# Sheet1.net
KiCad netlist of a schematic drawn in Altium Designer
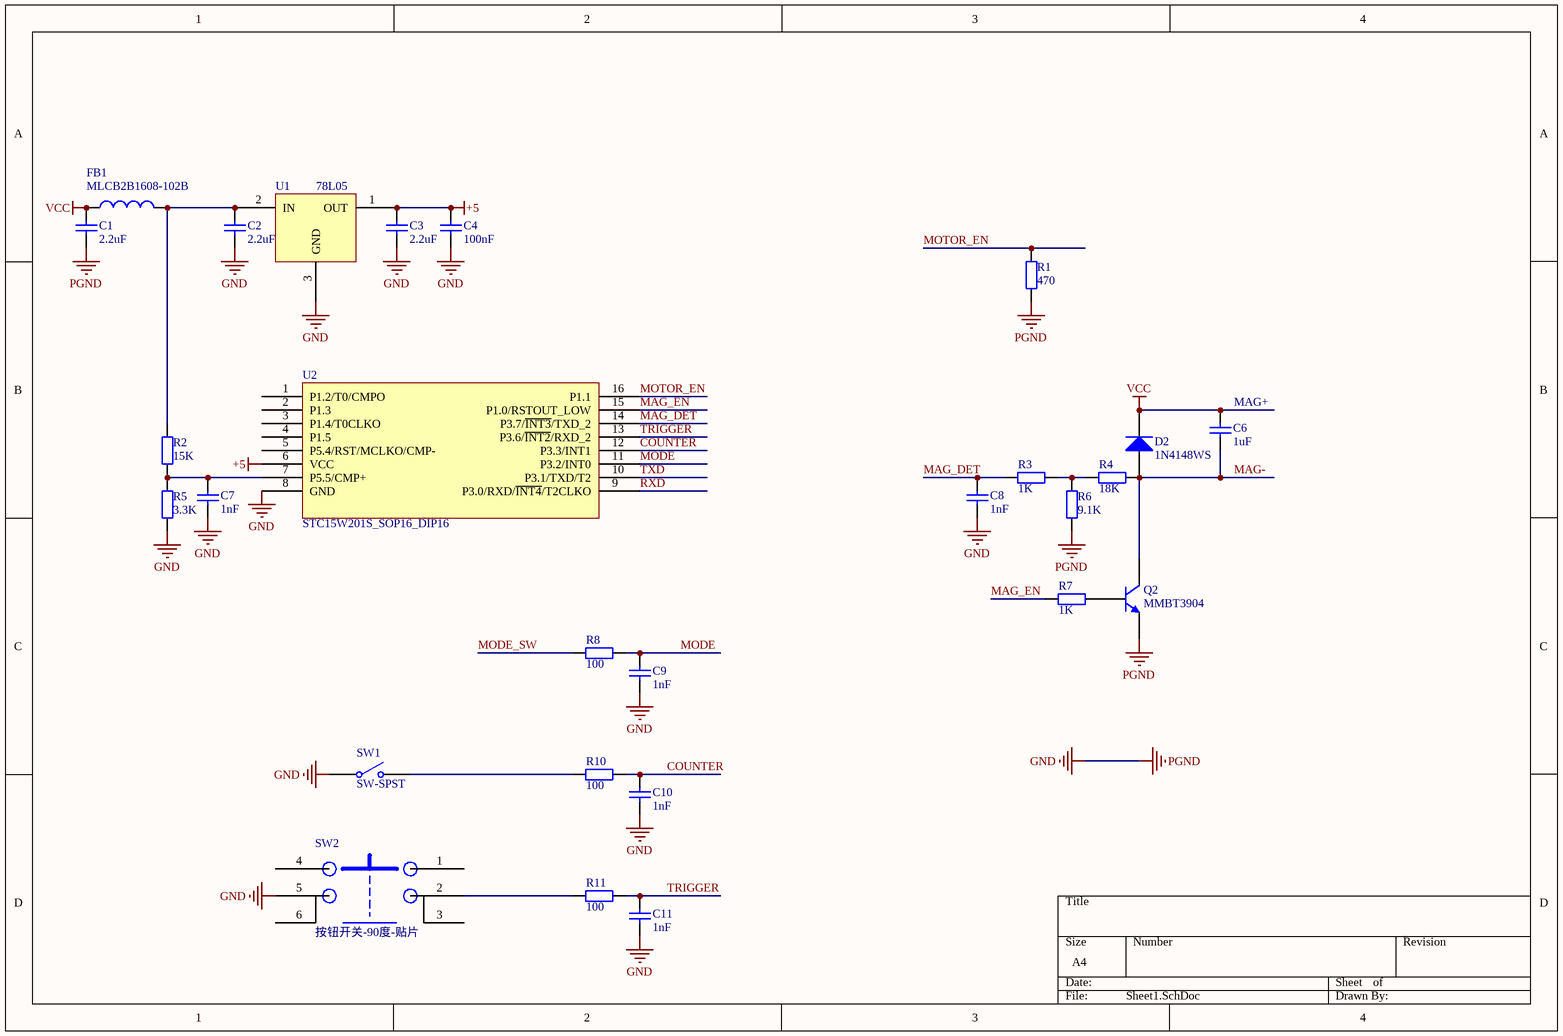
[diagram p0: Sheet1.SchDoc]

(export (version "E")
  (design (tool "Eeschema 10.0.6"))
  (components
    (comp (ref "C1")
      (value "2.2uF")
      (footprint "0805[cap]")
      (description "Chip Capacitor")
      (fields (field (name "Comment") "CT41L-0805-2C1-25V-225K"))
      (libsource (lib "passive") (part "Capacitor"))
    )
    (comp (ref "C2")
      (value "2.2uF")
      (footprint "0805[cap]")
      (description "Chip Capacitor")
      (fields (field (name "Comment") "CT41L-0805-2C1-25V-225K"))
      (libsource (lib "passive") (part "Capacitor"))
    )
    (comp (ref "C3")
      (value "2.2uF")
      (footprint "0805[cap]")
      (description "Chip Capacitor")
      (fields (field (name "Comment") "CT41L-0805-2C1-25V-225K"))
      (libsource (lib "passive") (part "Capacitor"))
    )
    (comp (ref "C4")
      (value "100nF")
      (footprint "0603[cap]")
      (description "Chip Capacitor")
      (fields (field (name "Comment") "CT41L-0603-2C1-50V-224K"))
      (libsource (lib "passive") (part "Capacitor"))
    )
    (comp (ref "C6")
      (value "1uF")
      (footprint "0603[cap]")
      (description "Chip Capacitor")
      (fields (field (name "Comment") "CT41L-0603-2C1-50V-224K"))
      (libsource (lib "passive") (part "Capacitor"))
    )
    (comp (ref "C7")
      (value "1nF")
      (footprint "0603[cap]")
      (description "Chip Capacitor")
      (fields (field (name "Comment") "CT41L-0603-2C1-50V-224K"))
      (libsource (lib "passive") (part "Capacitor"))
    )
    (comp (ref "C8")
      (value "1nF")
      (footprint "0603[cap]")
      (description "Chip Capacitor")
      (fields (field (name "Comment") "CT41L-0603-2C1-50V-224K"))
      (libsource (lib "passive") (part "Capacitor"))
    )
    (comp (ref "C9")
      (value "1nF")
      (footprint "0603[cap]")
      (description "Chip Capacitor")
      (fields (field (name "Comment") "CT41L-0603-2C1-50V-224K"))
      (libsource (lib "passive") (part "Capacitor"))
    )
    (comp (ref "C10")
      (value "1nF")
      (footprint "0603[cap]")
      (description "Chip Capacitor")
      (fields (field (name "Comment") "CT41L-0603-2C1-50V-224K"))
      (libsource (lib "passive") (part "Capacitor"))
    )
    (comp (ref "C11")
      (value "1nF")
      (footprint "0603[cap]")
      (description "Chip Capacitor")
      (fields (field (name "Comment") "CT41L-0603-2C1-50V-224K"))
      (libsource (lib "passive") (part "Capacitor"))
    )
    (comp (ref "D2")
      (value "1N4148WS")
      (footprint "SOD323")
      (description "Default Diode")
      (libsource (lib "Miscellaneous Devices") (part "Diode"))
    )
    (comp (ref "FB1")
      (value "MLCB2B1608-102B")
      (footprint "0603[bead]")
      (description "Chip Bead")
      (libsource (lib "passive") (part "bead"))
    )
    (comp (ref "Q2")
      (value "MMBT3904")
      (footprint "SOT23-3N")
      (description "NPN General Purpose Amplifier")
      (libsource (lib "transistor") (part "MMBT3904"))
    )
    (comp (ref "R1")
      (value "470")
      (footprint "0603[res]")
      (description "Resistor")
      (fields (field (name "Comment") "RMK1608MB102J"))
      (libsource (lib "") (part "Resistor_2"))
    )
    (comp (ref "R2")
      (value "15K")
      (footprint "0603[res]")
      (description "Resistor")
      (fields (field (name "Comment") "RMK1608MB102J"))
      (libsource (lib "") (part "Resistor_2"))
    )
    (comp (ref "R3")
      (value "1K")
      (footprint "0603[res]")
      (description "Resistor")
      (fields (field (name "Comment") "RMK1608MB102J"))
      (libsource (lib "passive") (part "Resistor"))
    )
    (comp (ref "R4")
      (value "18K")
      (footprint "0603[res]")
      (description "Resistor")
      (fields (field (name "Comment") "RMK1608MB102J"))
      (libsource (lib "") (part "Resistor_1"))
    )
    (comp (ref "R5")
      (value "3.3K")
      (footprint "0603[res]")
      (description "Resistor")
      (fields (field (name "Comment") "RMK1608MB102J"))
      (libsource (lib "") (part "Resistor_2"))
    )
    (comp (ref "R6")
      (value "9.1K")
      (footprint "0603[res]")
      (description "Resistor")
      (fields (field (name "Comment") "RMK1608MB102J"))
      (libsource (lib "") (part "Resistor_2"))
    )
    (comp (ref "R7")
      (value "1K")
      (footprint "0603[res]")
      (description "Resistor")
      (fields (field (name "Comment") "RMK1608MB102J"))
      (libsource (lib "passive") (part "Resistor"))
    )
    (comp (ref "R8")
      (value "100")
      (footprint "0603[res]")
      (description "Resistor")
      (fields (field (name "Comment") "RMK1608MB102J"))
      (libsource (lib "passive") (part "Resistor"))
    )
    (comp (ref "R10")
      (value "100")
      (footprint "0603[res]")
      (description "Resistor")
      (fields (field (name "Comment") "RMK1608MB102J"))
      (libsource (lib "passive") (part "Resistor"))
    )
    (comp (ref "R11")
      (value "100")
      (footprint "0603[res]")
      (description "Resistor")
      (fields (field (name "Comment") "RMK1608MB102J"))
      (libsource (lib "passive") (part "Resistor"))
    )
    (comp (ref "SW1")
      (value "SW-SPST")
      (footprint "JJJHRGG200NOPMRTR")
      (description "Single-Pole, Single-Throw Switch")
      (fields (field (name "PUBLISHER") "Altium Limited"))
      (libsource (lib "Miscellaneous Devices") (part "SW-SPST"))
    )
    (comp (ref "SW2")
      (value "按钮开关-90度-贴片")
      (footprint "按钮开关-90度-贴片")
      (libsource (lib "switch") (part "按钮开关-90度-贴片"))
    )
    (comp (ref "U1") (value "78L05") (footprint "SOT23-3N") (libsource (lib "power") (part "78L05")))
    (comp (ref "U2")
      (value "STC15W201S_SOP16_DIP16")
      (footprint "SOP16")
      (libsource (lib "stcmcu_altium_lib") (part "STC15W201S_SOP16_DIP16"))
    )
  )
  (nets
    (net (code "1") (name "+5") (class "Default")
      (node (ref "C3") (pin "1") (pinfunction "1_1") (pintype "passive"))
      (node (ref "C4") (pin "1") (pinfunction "1_1") (pintype "passive"))
      (node (ref "U1") (pin "1") (pinfunction "OUT_1") (pintype "passive"))
      (node (ref "U2") (pin "6") (pinfunction "VCC_6") (pintype "passive"))
    )
    (net (code "2") (name "/COUNTER") (class "Default")
      (node (ref "C10") (pin "1") (pinfunction "1_1") (pintype "passive"))
      (node (ref "R10") (pin "2") (pinfunction "2_2") (pintype "passive"))
      (node (ref "U2") (pin "12") (pinfunction "P3.3/INT1_12") (pintype "passive"))
    )
    (net (code "3") (name "/MAG-") (class "Default")
      (node (ref "C6") (pin "2") (pinfunction "2_2") (pintype "passive"))
      (node (ref "D2") (pin "1") (pinfunction "A_1") (pintype "passive"))
      (node (ref "Q2") (pin "3") (pinfunction "C_3") (pintype "passive"))
      (node (ref "R4") (pin "1") (pinfunction "1_1") (pintype "passive"))
    )
    (net (code "4") (name "/MAG_DET") (class "Default")
      (node (ref "C8") (pin "1") (pinfunction "1_1") (pintype "passive"))
      (node (ref "R3") (pin "1") (pinfunction "1_1") (pintype "passive"))
      (node (ref "U2") (pin "14") (pinfunction "P3.7/~{INT3}/TXD_2_14") (pintype "passive"))
    )
    (net (code "5") (name "/MAG_EN") (class "Default")
      (node (ref "R7") (pin "1") (pinfunction "1_1") (pintype "passive"))
      (node (ref "U2") (pin "15") (pinfunction "P1.0/RSTOUT_LOW_15") (pintype "passive"))
    )
    (net (code "6") (name "/MODE") (class "Default")
      (node (ref "C9") (pin "1") (pinfunction "1_1") (pintype "passive"))
      (node (ref "R8") (pin "2") (pinfunction "2_2") (pintype "passive"))
      (node (ref "U2") (pin "11") (pinfunction "P3.2/INT0_11") (pintype "passive"))
    )
    (net (code "7") (name "/MODE_SW") (class "Default")
      (node (ref "R8") (pin "1") (pinfunction "1_1") (pintype "passive"))
    )
    (net (code "8") (name "/MOTOR_EN") (class "Default")
      (node (ref "R1") (pin "2") (pinfunction "2_2") (pintype "passive"))
      (node (ref "U2") (pin "16") (pinfunction "P1.1_16") (pintype "passive"))
    )
    (net (code "9") (name "/RXD") (class "Default")
      (node (ref "U2") (pin "9") (pinfunction "P3.0/RXD/~{INT4}/T2CLKO_9") (pintype "passive"))
    )
    (net (code "10") (name "/TRIGGER") (class "Default")
      (node (ref "C11") (pin "1") (pinfunction "1_1") (pintype "passive"))
      (node (ref "R11") (pin "2") (pinfunction "2_2") (pintype "passive"))
      (node (ref "U2") (pin "13") (pinfunction "P3.6/~{INT2}/RXD_2_13") (pintype "passive"))
    )
    (net (code "11") (name "/TXD") (class "Default")
      (node (ref "U2") (pin "10") (pinfunction "P3.1/TXD/T2_10") (pintype "passive"))
    )
    (net (code "12") (name "GND") (class "Default")
      (node (ref "C1") (pin "2") (pinfunction "2_2") (pintype "passive"))
      (node (ref "C10") (pin "2") (pinfunction "2_2") (pintype "passive"))
      (node (ref "C11") (pin "2") (pinfunction "2_2") (pintype "passive"))
      (node (ref "C2") (pin "2") (pinfunction "2_2") (pintype "passive"))
      (node (ref "C3") (pin "2") (pinfunction "2_2") (pintype "passive"))
      (node (ref "C4") (pin "2") (pinfunction "2_2") (pintype "passive"))
      (node (ref "C7") (pin "2") (pinfunction "2_2") (pintype "passive"))
      (node (ref "C8") (pin "2") (pinfunction "2_2") (pintype "passive"))
      (node (ref "C9") (pin "2") (pinfunction "2_2") (pintype "passive"))
      (node (ref "Q2") (pin "2") (pinfunction "E_2") (pintype "passive"))
      (node (ref "R1") (pin "1") (pinfunction "1_1") (pintype "passive"))
      (node (ref "R5") (pin "1") (pinfunction "1_1") (pintype "passive"))
      (node (ref "R6") (pin "1") (pinfunction "1_1") (pintype "passive"))
      (node (ref "SW1") (pin "1") (pinfunction "COMMON_1") (pintype "passive"))
      (node (ref "SW2") (pin "5") (pinfunction "5_5") (pintype "passive"))
      (node (ref "U1") (pin "3") (pinfunction "GND_3") (pintype "passive"))
      (node (ref "U2") (pin "8") (pinfunction "GND_8") (pintype "passive"))
    )
    (net (code "13") (name "Net-(Q2-B)") (class "Default")
      (node (ref "Q2") (pin "1") (pinfunction "B_1") (pintype "passive"))
      (node (ref "R7") (pin "2") (pinfunction "2_2") (pintype "passive"))
    )
    (net (code "14") (name "Net-(R3-Pad2)") (class "Default")
      (node (ref "R3") (pin "2") (pinfunction "2_2") (pintype "passive"))
      (node (ref "R4") (pin "2") (pinfunction "2_2") (pintype "passive"))
      (node (ref "R6") (pin "2") (pinfunction "2_2") (pintype "passive"))
    )
    (net (code "15") (name "Net-(R11-Pad1)") (class "Default")
      (node (ref "R11") (pin "1") (pinfunction "1_1") (pintype "passive"))
      (node (ref "SW2") (pin "2") (pintype "passive"))
    )
    (net (code "16") (name "Net-(SW1-NO)") (class "Default")
      (node (ref "R10") (pin "1") (pinfunction "1_1") (pintype "passive"))
      (node (ref "SW1") (pin "2") (pinfunction "NO_2") (pintype "passive"))
    )
    (net (code "17") (name "Net-(U1-IN)") (class "Default")
      (node (ref "C2") (pin "1") (pinfunction "1_1") (pintype "passive"))
      (node (ref "FB1") (pin "2") (pinfunction "2_2") (pintype "passive"))
      (node (ref "R2") (pin "2") (pinfunction "2_2") (pintype "passive"))
      (node (ref "U1") (pin "2") (pinfunction "IN_2") (pintype "passive"))
    )
    (net (code "18") (name "Net-(U2-P5.5{slash}CMP+)") (class "Default")
      (node (ref "C7") (pin "1") (pinfunction "1_1") (pintype "passive"))
      (node (ref "R2") (pin "1") (pinfunction "1_1") (pintype "passive"))
      (node (ref "R5") (pin "2") (pinfunction "2_2") (pintype "passive"))
      (node (ref "U2") (pin "7") (pinfunction "P5.5/CMP+_7") (pintype "passive"))
    )
    (net (code "19") (name "VCC") (class "Default")
      (node (ref "C1") (pin "1") (pinfunction "1_1") (pintype "passive"))
      (node (ref "C6") (pin "1") (pinfunction "1_1") (pintype "passive"))
      (node (ref "D2") (pin "2") (pinfunction "K_2") (pintype "passive"))
      (node (ref "FB1") (pin "1") (pinfunction "1_1") (pintype "passive"))
    )
    (net (code "20") (name "unconnected-(SW2-Pad1)") (class "Default")
      (node (ref "SW2") (pin "1") (pintype "passive"))
    )
    (net (code "21") (name "unconnected-(SW2-Pad3)") (class "Default")
      (node (ref "SW2") (pin "3") (pintype "passive"))
    )
    (net (code "22") (name "unconnected-(SW2-Pad4)") (class "Default")
      (node (ref "SW2") (pin "4") (pinfunction "4_4") (pintype "passive"))
    )
    (net (code "23") (name "unconnected-(SW2-Pad6)") (class "Default")
      (node (ref "SW2") (pin "6") (pinfunction "6_6") (pintype "passive"))
    )
    (net (code "24") (name "unconnected-(U2-P1.2{slash}T0{slash}CMPO-Pad1)") (class "Default")
      (node (ref "U2") (pin "1") (pinfunction "P1.2/T0/CMPO_1") (pintype "passive"))
    )
    (net (code "25") (name "unconnected-(U2-P1.3-Pad2)") (class "Default")
      (node (ref "U2") (pin "2") (pinfunction "P1.3_2") (pintype "passive"))
    )
    (net (code "26") (name "unconnected-(U2-P1.4{slash}T0CLKO-Pad3)") (class "Default")
      (node (ref "U2") (pin "3") (pinfunction "P1.4/T0CLKO_3") (pintype "passive"))
    )
    (net (code "27") (name "unconnected-(U2-P1.5-Pad4)") (class "Default")
      (node (ref "U2") (pin "4") (pinfunction "P1.5_4") (pintype "passive"))
    )
    (net (code "28") (name "unconnected-(U2-P5.4{slash}RST{slash}MCLKO{slash}CMP--Pad5)") (class "Default")
      (node (ref "U2") (pin "5") (pinfunction "P5.4/RST/MCLKO/CMP-_5") (pintype "passive"))
    )
  )
)
